# Power.net
KiCad netlist of a schematic drawn in Altium Designer
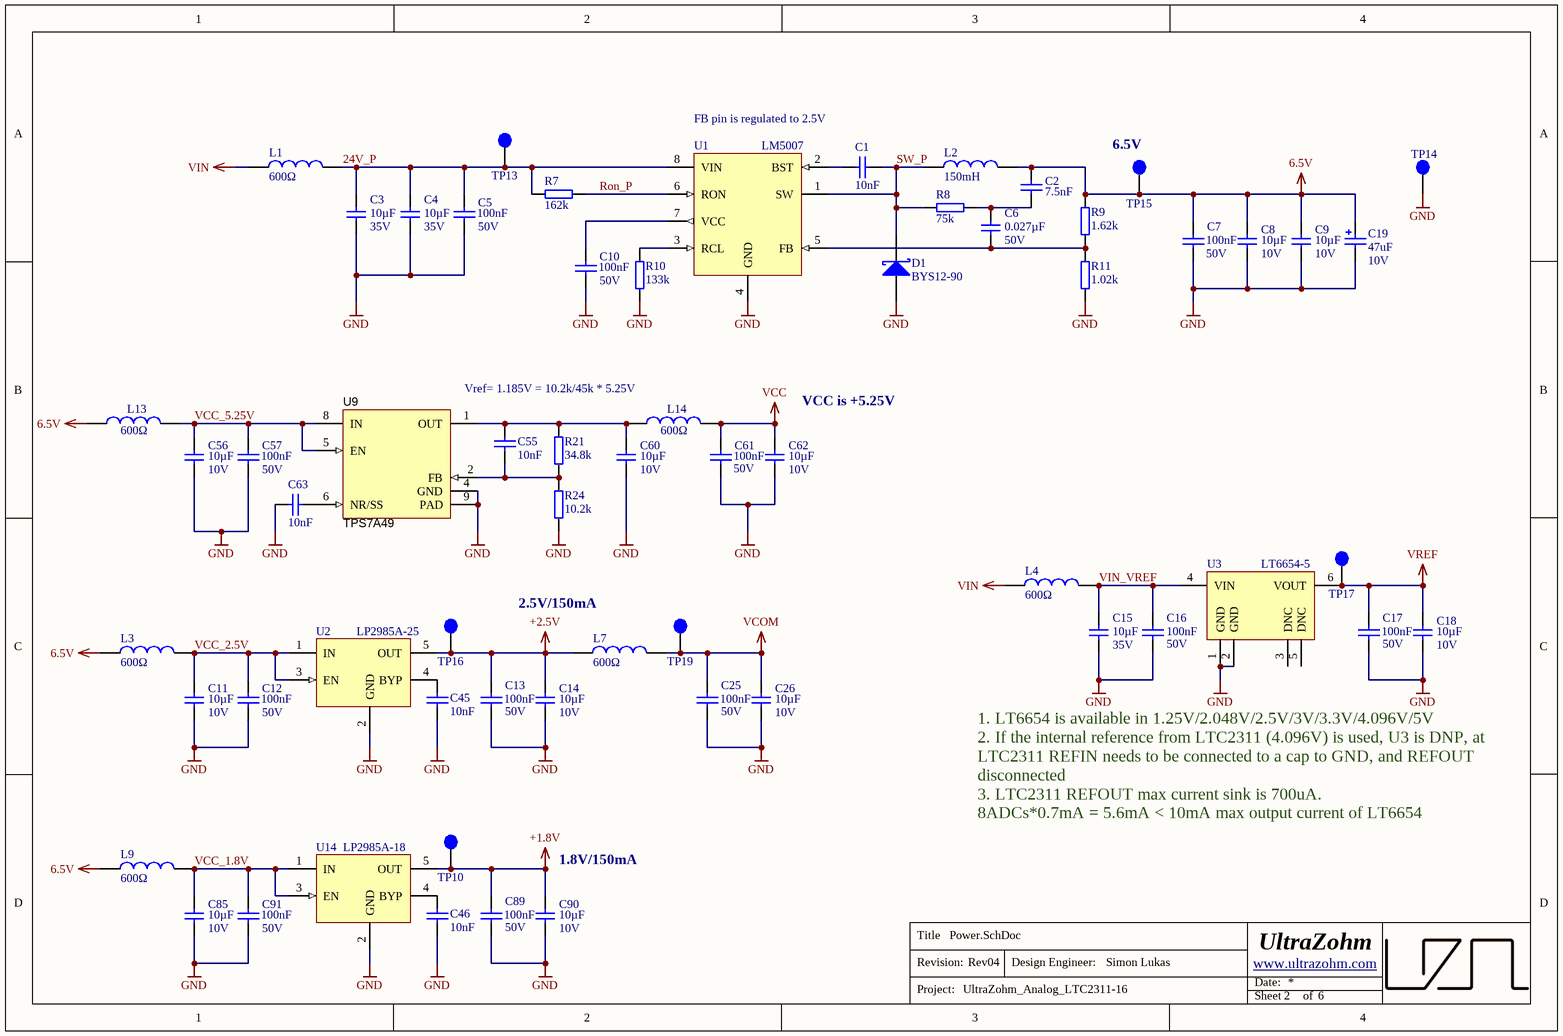
[diagram p0: Power.SchDoc]

(export (version "E")
  (design (tool "Eeschema 10.0.6"))
  (components
    (comp (ref "C1")
      (value "10nF")
      (footprint "CAPC1608X07N")
      (fields (field (name "MF") "Würth") (field (name "MPN") "885012206065") (field (name "VOLTAGE") "25V"))
      (libsource (lib "UltraZohm_ADC") (part "Cap_0603"))
    )
    (comp (ref "C2")
      (value "7.5nF")
      (footprint "CAPC1608X07N")
      (fields
        (field (name "MF") "KEMET")
        (field (name "MPN") "C0603C752J3GACTU")
        (field (name "VOLTAGE") "25V")
      )
      (libsource (lib "UltraZohm_ADC") (part "Cap_0603"))
    )
    (comp (ref "C3")
      (value "10µF")
      (footprint "C_1206")
      (description "Capacitor 1206")
      (fields (field (name "TOLERANCE") "20%") (field (name "MF") "AVX") (field (name "VOLTAGE") "35V"))
      (libsource (lib "UltraZohm_ADC") (part "C_1206"))
    )
    (comp (ref "C4")
      (value "10µF")
      (footprint "C_1206")
      (description "Capacitor 1206")
      (fields (field (name "TOLERANCE") "20%") (field (name "MF") "AVX") (field (name "VOLTAGE") "35V"))
      (libsource (lib "UltraZohm_ADC") (part "C_1206"))
    )
    (comp (ref "C5")
      (value "100nF")
      (footprint "CAPC1608X07N")
      (fields
        (field (name "MF") "Yageo")
        (field (name "MPN") "CC0603KRX7R9BB104")
        (field (name "VOLTAGE") "50V")
        (field (name "TOLERANCE") "10%")
      )
      (libsource (lib "UltraZohm_ADC") (part "Cap_0603"))
    )
    (comp (ref "C6")
      (value "0.027µF")
      (footprint "C_1206")
      (description "Capacitor 1206")
      (fields
        (field (name "TOLERANCE") "5%")
        (field (name "MF") "Murata")
        (field (name "VOLTAGE") "50V")
        (field (name "CREATED") "2018_06_25_AGeiger")
      )
      (libsource (lib "UltraZohm_ADC") (part "C_1206"))
    )
    (comp (ref "C7")
      (value "100nF")
      (footprint "CAPC1608X07N")
      (fields
        (field (name "MF") "Yageo")
        (field (name "MPN") "CC0603KRX7R9BB104")
        (field (name "VOLTAGE") "50V")
      )
      (libsource (lib "UltraZohm_ADC") (part "Cap_0603"))
    )
    (comp (ref "C8")
      (value "10µF")
      (footprint "C_1206")
      (description "Capacitor 1206")
      (fields
        (field (name "TOLERANCE") "10%")
        (field (name "MF") "Samsung Electro-Mechanics")
        (field (name "VOLTAGE") "10V")
        (field (name "CREATED") "2020_09_17_Liegmann")
      )
      (libsource (lib "UltraZohm_ADC") (part "C_1206"))
    )
    (comp (ref "C9")
      (value "10µF")
      (footprint "C_1206")
      (description "Capacitor 1206")
      (fields
        (field (name "TOLERANCE") "10%")
        (field (name "MF") "Samsung Electro-Mechanics")
        (field (name "VOLTAGE") "10V")
        (field (name "CREATED") "2020_09_17_Liegmann")
      )
      (libsource (lib "UltraZohm_ADC") (part "C_1206"))
    )
    (comp (ref "C10")
      (value "100nF")
      (footprint "CAPC1608X07N")
      (fields
        (field (name "MF") "Yageo")
        (field (name "MPN") "CC0603KRX7R9BB104")
        (field (name "VOLTAGE") "50V")
        (field (name "TOLERANCE") "10%")
      )
      (libsource (lib "UltraZohm_ADC") (part "Cap_0603"))
    )
    (comp (ref "C11")
      (value "10µF")
      (footprint "C_1206")
      (description "Capacitor 1206")
      (fields
        (field (name "TOLERANCE") "10%")
        (field (name "MF") "Samsung Electro-Mechanics")
        (field (name "VOLTAGE") "10V")
        (field (name "CREATED") "2020_09_17_Liegmann")
      )
      (libsource (lib "UltraZohm_ADC") (part "C_1206"))
    )
    (comp (ref "C12")
      (value "100nF")
      (footprint "CAPC1608X07N")
      (fields
        (field (name "MF") "Yageo")
        (field (name "MPN") "CC0603KRX7R9BB104")
        (field (name "VOLTAGE") "50V")
        (field (name "TOLERANCE") "10%")
      )
      (libsource (lib "UltraZohm_ADC") (part "Cap_0603"))
    )
    (comp (ref "C13")
      (value "100nF")
      (footprint "CAPC1608X07N")
      (fields
        (field (name "MF") "Yageo")
        (field (name "MPN") "CC0603KRX7R9BB104")
        (field (name "VOLTAGE") "50V")
      )
      (libsource (lib "UltraZohm_ADC") (part "Cap_0603"))
    )
    (comp (ref "C14")
      (value "10µF")
      (footprint "C_1206")
      (description "Capacitor 1206")
      (fields
        (field (name "TOLERANCE") "10%")
        (field (name "MF") "Samsung Electro-Mechanics")
        (field (name "VOLTAGE") "10V")
        (field (name "CREATED") "2020_09_17_Liegmann")
      )
      (libsource (lib "UltraZohm_ADC") (part "C_1206"))
    )
    (comp (ref "C15")
      (value "10µF")
      (footprint "C_1206")
      (description "Capacitor 1206")
      (fields (field (name "TOLERANCE") "20%") (field (name "MF") "AVX") (field (name "VOLTAGE") "35V"))
      (libsource (lib "UltraZohm_ADC") (part "C_1206"))
    )
    (comp (ref "C16")
      (value "100nF")
      (footprint "CAPC1608X07N")
      (fields
        (field (name "MF") "Yageo")
        (field (name "MPN") "CC0603KRX7R9BB104")
        (field (name "VOLTAGE") "50V")
      )
      (libsource (lib "UltraZohm_ADC") (part "Cap_0603"))
    )
    (comp (ref "C17")
      (value "100nF")
      (footprint "CAPC1608X07N")
      (fields
        (field (name "MF") "Yageo")
        (field (name "MPN") "CC0603KRX7R9BB104")
        (field (name "VOLTAGE") "50V")
      )
      (libsource (lib "UltraZohm_ADC") (part "Cap_0603"))
    )
    (comp (ref "C18")
      (value "10µF")
      (footprint "C_1206")
      (description "Capacitor 1206")
      (fields
        (field (name "TOLERANCE") "10%")
        (field (name "MF") "Samsung Electro-Mechanics")
        (field (name "VOLTAGE") "10V")
        (field (name "CREATED") "2020_09_17_Liegmann")
      )
      (libsource (lib "UltraZohm_ADC") (part "C_1206"))
    )
    (comp (ref "C19")
      (value "47uF")
      (footprint "WCAP-ASLI_5x5.5")
      (description "WCAP-ASLI Aluminum Electrolytic Capacitor, V-Chip, SMT, D5xH5.5mm, 47uF, 10V")
      (fields
        (field (name "MPN") "865080242004")
        (field (name "MF") "Wurth Elektronik")
        (field (name "VOLTAGE") "10V")
      )
      (libsource (lib "UltraZohm_ADC") (part "865080142007"))
    )
    (comp (ref "C25")
      (value "100nF")
      (footprint "CAPC1608X07N")
      (fields
        (field (name "MF") "Yageo")
        (field (name "MPN") "CC0603KRX7R9BB104")
        (field (name "VOLTAGE") "50V")
      )
      (libsource (lib "UltraZohm_ADC") (part "Cap_0603"))
    )
    (comp (ref "C26")
      (value "10µF")
      (footprint "C_1206")
      (description "Capacitor 1206")
      (fields
        (field (name "TOLERANCE") "10%")
        (field (name "MF") "Samsung Electro-Mechanics")
        (field (name "VOLTAGE") "10V")
        (field (name "CREATED") "2020_09_17_Liegmann")
      )
      (libsource (lib "UltraZohm_ADC") (part "C_1206"))
    )
    (comp (ref "C45")
      (value "10nF")
      (footprint "CAPC1608X07N")
      (fields (field (name "MF") "Würth") (field (name "MPN") "885012206065") (field (name "VOLTAGE") "25V"))
      (libsource (lib "UltraZohm_ADC") (part "Cap_0603"))
    )
    (comp (ref "C46")
      (value "10nF")
      (footprint "CAPC1608X07N")
      (fields (field (name "MF") "Würth") (field (name "MPN") "885012206065") (field (name "VOLTAGE") "25V"))
      (libsource (lib "UltraZohm_ADC") (part "Cap_0603"))
    )
    (comp (ref "C55")
      (value "10nF")
      (footprint "CAPC1608X07N")
      (fields
        (field (name "MF") "Würth Elektronik")
        (field (name "MPN") "885012206065")
        (field (name "VOLTAGE") "25V")
      )
      (libsource (lib "UltraZohm_ADC") (part "Cap_0603"))
    )
    (comp (ref "C56")
      (value "10µF")
      (footprint "C_1206")
      (description "Capacitor 1206")
      (fields
        (field (name "TOLERANCE") "10%")
        (field (name "MF") "Samsung Electro-Mechanics")
        (field (name "VOLTAGE") "10V")
        (field (name "CREATED") "2020_09_17_Liegmann")
      )
      (libsource (lib "UltraZohm_ADC") (part "C_1206"))
    )
    (comp (ref "C57")
      (value "100nF")
      (footprint "CAPC1608X07N")
      (fields
        (field (name "MF") "Yageo")
        (field (name "MPN") "CC0603KRX7R9BB104")
        (field (name "VOLTAGE") "50V")
        (field (name "TOLERANCE") "10%")
      )
      (libsource (lib "UltraZohm_ADC") (part "Cap_0603"))
    )
    (comp (ref "C60")
      (value "10µF")
      (footprint "C_1206")
      (description "Capacitor 1206")
      (fields
        (field (name "TOLERANCE") "10%")
        (field (name "MF") "Samsung Electro-Mechanics")
        (field (name "VOLTAGE") "10V")
        (field (name "CREATED") "2020_09_17_Liegmann")
      )
      (libsource (lib "UltraZohm_ADC") (part "C_1206"))
    )
    (comp (ref "C61")
      (value "100nF")
      (footprint "CAPC1608X07N")
      (fields
        (field (name "MF") "Yageo")
        (field (name "MPN") "CC0603KRX7R9BB104")
        (field (name "VOLTAGE") "50V")
        (field (name "TOLERANCE") "10%")
      )
      (libsource (lib "UltraZohm_ADC") (part "Cap_0603"))
    )
    (comp (ref "C62")
      (value "10µF")
      (footprint "C_1206")
      (description "Capacitor 1206")
      (fields
        (field (name "TOLERANCE") "10%")
        (field (name "MF") "Samsung Electro-Mechanics")
        (field (name "VOLTAGE") "10V")
        (field (name "CREATED") "2020_09_17_Liegmann")
      )
      (libsource (lib "UltraZohm_ADC") (part "C_1206"))
    )
    (comp (ref "C63")
      (value "10nF")
      (footprint "CAPC1608X07N")
      (fields
        (field (name "MF") "Würth Elektronik")
        (field (name "MPN") "885012206065")
        (field (name "VOLTAGE") "25V")
      )
      (libsource (lib "UltraZohm_ADC") (part "Cap_0603"))
    )
    (comp (ref "C85")
      (value "10µF")
      (footprint "C_1206")
      (description "Capacitor 1206")
      (fields
        (field (name "TOLERANCE") "10%")
        (field (name "MF") "Samsung Electro-Mechanics")
        (field (name "VOLTAGE") "10V")
        (field (name "CREATED") "2020_09_17_Liegmann")
      )
      (libsource (lib "UltraZohm_ADC") (part "C_1206"))
    )
    (comp (ref "C89")
      (value "100nF")
      (footprint "CAPC1608X07N")
      (fields
        (field (name "MF") "Yageo")
        (field (name "MPN") "CC0603KRX7R9BB104")
        (field (name "VOLTAGE") "50V")
      )
      (libsource (lib "UltraZohm_ADC") (part "Cap_0603"))
    )
    (comp (ref "C90")
      (value "10µF")
      (footprint "C_1206")
      (description "Capacitor 1206")
      (fields
        (field (name "TOLERANCE") "10%")
        (field (name "MF") "Samsung Electro-Mechanics")
        (field (name "VOLTAGE") "10V")
        (field (name "CREATED") "2020_09_17_Liegmann")
      )
      (libsource (lib "UltraZohm_ADC") (part "C_1206"))
    )
    (comp (ref "C91")
      (value "100nF")
      (footprint "CAPC1608X07N")
      (fields
        (field (name "MF") "Yageo")
        (field (name "MPN") "CC0603KRX7R9BB104")
        (field (name "VOLTAGE") "50V")
        (field (name "TOLERANCE") "10%")
      )
      (libsource (lib "UltraZohm_ADC") (part "Cap_0603"))
    )
    (comp (ref "D1")
      (value "BYS12-90")
      (footprint "DIOM4227X23N")
      (description "Schottky Diode")
      (fields (field (name "MF") "Vishay") (field (name "MPN") "BYS12-90-E3/TR3"))
      (libsource (lib "UltraZohm_ADC") (part "BYS12-90"))
    )
    (comp (ref "L1")
      (value "600Ω")
      (footprint "WE-CBF_0805_High Current")
      (description "WE-CBF SMD EMI Suppression Ferrite Bead, 0805, 600Ω")
      (fields (field (name "MF") "Wurth Elektronik") (field (name "MPN") "742792040"))
      (libsource (lib "UltraZohm_ADC") (part "WE-CBF, 742792040"))
    )
    (comp (ref "L2")
      (value "150mH")
      (footprint "SMT_inductor_1050_Performance")
      (description "SMT power Inductor, 150uH, 320m DRC")
      (fields (field (name "MF") "EPCOS / TDK") (field (name "MPN") "B82464G4154M"))
      (libsource (lib "UltraZohm_ADC") (part "B82464G4154M"))
    )
    (comp (ref "L3")
      (value "600Ω")
      (footprint "WE-CBF_0805_High Current")
      (description "WE-CBF SMD EMI Suppression Ferrite Bead, 0805, 600Ω")
      (fields (field (name "MF") "Wurth Elektronik") (field (name "MPN") "742792040"))
      (libsource (lib "UltraZohm_ADC") (part "WE-CBF, 742792040"))
    )
    (comp (ref "L4")
      (value "600Ω")
      (footprint "WE-CBF_0805_High Current")
      (description "WE-CBF SMD EMI Suppression Ferrite Bead, 0805, 600Ω")
      (fields (field (name "MF") "Wurth Elektronik") (field (name "MPN") "742792040"))
      (libsource (lib "UltraZohm_ADC") (part "WE-CBF, 742792040"))
    )
    (comp (ref "L7")
      (value "600Ω")
      (footprint "WE-CBF_0805_High Current")
      (description "WE-CBF SMD EMI Suppression Ferrite Bead, 0805, 600Ω")
      (fields (field (name "MF") "Wurth Elektronik") (field (name "MPN") "742792040"))
      (libsource (lib "UltraZohm_ADC") (part "WE-CBF, 742792040"))
    )
    (comp (ref "L9")
      (value "600Ω")
      (footprint "WE-CBF_0805_High Current")
      (description "WE-CBF SMD EMI Suppression Ferrite Bead, 0805, 600Ω")
      (fields (field (name "MF") "Wurth Elektronik") (field (name "MPN") "742792040"))
      (libsource (lib "UltraZohm_ADC") (part "WE-CBF, 742792040"))
    )
    (comp (ref "L13")
      (value "600Ω")
      (footprint "WE-CBF_0805_High Current")
      (description "WE-CBF SMD EMI Suppression Ferrite Bead, 0805, 600Ω")
      (fields (field (name "MF") "Würth Elektronik") (field (name "MPN") "742792040"))
      (libsource (lib "UltraZohm_ADC") (part "WE-CBF, 742792040"))
    )
    (comp (ref "L14")
      (value "600Ω")
      (footprint "WE-CBF_0805_High Current")
      (description "WE-CBF SMD EMI Suppression Ferrite Bead, 0805, 600Ω")
      (fields (field (name "MF") "Würth Elektronik") (field (name "MPN") "742792040"))
      (libsource (lib "UltraZohm_ADC") (part "WE-CBF, 742792040"))
    )
    (comp (ref "R7")
      (value "162k")
      (footprint "RESC1608X06N")
      (fields (field (name "MF") "Bourns") (field (name "MPN") "CR0603-FX-1623ELF"))
      (libsource (lib "UltraZohm_ADC") (part "R_0603"))
    )
    (comp (ref "R8")
      (value "75k")
      (footprint "RESC1608X06N")
      (fields (field (name "MF") "Yageo") (field (name "MPN") "AC0603FR-1375KL"))
      (libsource (lib "UltraZohm_ADC") (part "R_0603"))
    )
    (comp (ref "R9")
      (value "1.62k")
      (footprint "RESC1608X06N")
      (fields
        (field (name "MF") "Bourns")
        (field (name "MPN") "CR0603-FX-1621ELF")
        (field (name "TOLERANCE") "1%")
      )
      (libsource (lib "UltraZohm_ADC") (part "R_0603"))
    )
    (comp (ref "R10")
      (value "133k")
      (footprint "RESC1608X06N")
      (fields (field (name "MF") "Bourns") (field (name "MPN") "CR0603-FX-1333ELF"))
      (libsource (lib "UltraZohm_ADC") (part "R_0603"))
    )
    (comp (ref "R11")
      (value "1.02k")
      (footprint "RESC1608X06N")
      (fields
        (field (name "MF") "Bourns")
        (field (name "MPN") "CR0603-FX-1021ELF")
        (field (name "TOLERANCE") "1%")
      )
      (libsource (lib "UltraZohm_ADC") (part "R_0603"))
    )
    (comp (ref "R21")
      (value "34.8k")
      (footprint "RESC1608X06N")
      (fields
        (field (name "MF") "Bourns")
        (field (name "MPN") "CR0603-FX-3482ELF")
        (field (name "TOLERANCE") "1%")
      )
      (libsource (lib "UltraZohm_ADC") (part "R_0603"))
    )
    (comp (ref "R24")
      (value "10.2k")
      (footprint "RESC1608X06N")
      (fields
        (field (name "MF") "Bourns")
        (field (name "MPN") "CR0603-FX-1022ELF")
        (field (name "TOLERANCE") "1%")
      )
      (libsource (lib "UltraZohm_ADC") (part "R_0603"))
    )
    (comp (ref "TP10")
      (value "+1.8V")
      (footprint "TP_1mm")
      (description "Testpoint 1mm")
      (fields (field (name "CREATED") "2018_06_25_AGeiger"))
      (libsource (lib "UltraZOhm_CarrierBoard") (part "TP_1mm"))
    )
    (comp (ref "TP13")
      (value "VIN")
      (footprint "TP_1mm")
      (description "Testpoint 1mm")
      (fields (field (name "CREATED") "2018_06_25_AGeiger"))
      (libsource (lib "UltraZOhm_CarrierBoard") (part "TP_1mm"))
    )
    (comp (ref "TP14")
      (value "GND")
      (footprint "TP_1mm")
      (description "Testpoint 1mm")
      (fields (field (name "CREATED") "2018_06_25_AGeiger"))
      (libsource (lib "UltraZOhm_CarrierBoard") (part "TP_1mm"))
    )
    (comp (ref "TP15")
      (value "+5V")
      (footprint "TP_1mm")
      (description "Testpoint 1mm")
      (fields (field (name "CREATED") "2018_06_25_AGeiger"))
      (libsource (lib "UltraZOhm_CarrierBoard") (part "TP_1mm"))
    )
    (comp (ref "TP16")
      (value "OVCC")
      (footprint "TP_1mm")
      (description "Testpoint 1mm")
      (fields (field (name "CREATED") "2018_06_25_AGeiger"))
      (libsource (lib "UltraZOhm_CarrierBoard") (part "TP_1mm"))
    )
    (comp (ref "TP17")
      (value "VREF")
      (footprint "TP_1mm")
      (description "Testpoint 1mm")
      (fields (field (name "CREATED") "2018_06_25_AGeiger"))
      (libsource (lib "UltraZOhm_CarrierBoard") (part "TP_1mm"))
    )
    (comp (ref "TP19")
      (value "VCOM")
      (footprint "TP_1mm")
      (description "Testpoint 1mm")
      (fields (field (name "CREATED") "2018_06_25_AGeiger"))
      (libsource (lib "UltraZOhm_CarrierBoard") (part "TP_1mm"))
    )
    (comp (ref "U1")
      (value "LM5007")
      (footprint "TSOP65P490X110-8N")
      (description "Buck Converter, 9-75Vin, 2.5-73Vout")
      (fields (field (name "MF") "Texas Instruments") (field (name "MPN") "LM5007MM/NOPB"))
      (libsource (lib "UltraZohm_ADC") (part "LM5007"))
    )
    (comp (ref "U2")
      (value "LP2985A-25")
      (footprint "SOT95P250X110-5N")
      (description "150mA, LDO, Vout = 2.5V, Vin,max = 16V")
      (fields (field (name "MF") "Texas Instruments"))
      (libsource (lib "UltraZohm_ADC") (part "LP2985A-25"))
    )
    (comp (ref "U3")
      (value "LT6654-5")
      (footprint "SOT95P280X100-6N")
      (fields (field (name "MF") "Analog Devices") (field (name "MPN") "LT6654AIS6-5#TRMPBF"))
      (libsource (lib "UltraZohm_ADC") (part "LT6654"))
    )
    (comp (ref "U9")
      (value "TPS7A49")
      (footprint "DGN0008D_N")
      (description "+36V, +150mA, Ultralow-Noise, Positive LINEAR REGULATOR, DGN0008D")
      (fields (field (name "MPN") "TPS7A4901DGN") (field (name "MF") "Texas Instruments"))
      (libsource (lib "UltraZohm_ADC") (part "TPS7A4901DGN"))
    )
    (comp (ref "U14")
      (value "LP2985A-18")
      (footprint "SOT95P250X110-5N")
      (description "150mA, LDO, Vout = 1.8V , Vin,max = 16V")
      (libsource (lib "UltraZohm_ADC") (part "LP2985A-18"))
    )
  )
  (nets
    (net (code "1") (name "+1.8V") (class "Default")
      (node (ref "C89") (pin "1") (pinfunction "1_1") (pintype "passive"))
      (node (ref "C90") (pin "2") (pinfunction "2_2") (pintype "passive"))
      (node (ref "TP10") (pin "1") (pintype "passive"))
      (node (ref "U14") (pin "5") (pinfunction "OUT_5") (pintype "power_in"))
    )
    (net (code "2") (name "+2.5V") (class "Default")
      (node (ref "C13") (pin "1") (pinfunction "1_1") (pintype "passive"))
      (node (ref "C14") (pin "2") (pinfunction "2_2") (pintype "passive"))
      (node (ref "L7") (pin "1") (pinfunction "1_1") (pintype "passive"))
      (node (ref "TP16") (pin "1") (pintype "passive"))
      (node (ref "U2") (pin "5") (pinfunction "OUT_5") (pintype "power_in"))
    )
    (net (code "3") (name "/24V_P") (class "Default")
      (node (ref "C3") (pin "2") (pinfunction "2_2") (pintype "passive"))
      (node (ref "C4") (pin "2") (pinfunction "2_2") (pintype "passive"))
      (node (ref "C5") (pin "1") (pinfunction "1_1") (pintype "passive"))
      (node (ref "L1") (pin "2") (pinfunction "2_2") (pintype "passive"))
      (node (ref "R7") (pin "1") (pintype "passive"))
      (node (ref "TP13") (pin "1") (pintype "passive"))
      (node (ref "U1") (pin "8") (pinfunction "VIN_8") (pintype "power_in"))
    )
    (net (code "4") (name "/Ron_P") (class "Default")
      (node (ref "R7") (pin "2") (pintype "passive"))
      (node (ref "U1") (pin "6") (pinfunction "RON_6") (pintype "input"))
    )
    (net (code "5") (name "/SW_P") (class "Default")
      (node (ref "C1") (pin "2") (pinfunction "2_2") (pintype "passive"))
      (node (ref "D1") (pin "1") (pinfunction "K_1") (pintype "passive"))
      (node (ref "L2") (pin "1") (pinfunction "1_1") (pintype "passive"))
      (node (ref "R8") (pin "1") (pintype "passive"))
      (node (ref "U1") (pin "1") (pinfunction "SW_1") (pintype "power_in"))
    )
    (net (code "6") (name "/VCC_1.8V") (class "Default")
      (node (ref "C85") (pin "2") (pinfunction "2_2") (pintype "passive"))
      (node (ref "C91") (pin "1") (pinfunction "1_1") (pintype "passive"))
      (node (ref "L9") (pin "2") (pinfunction "2_2") (pintype "passive"))
      (node (ref "U14") (pin "1") (pinfunction "IN_1") (pintype "power_in"))
      (node (ref "U14") (pin "3") (pinfunction "EN_3") (pintype "input"))
    )
    (net (code "7") (name "/VCC_2.5V") (class "Default")
      (node (ref "C11") (pin "2") (pinfunction "2_2") (pintype "passive"))
      (node (ref "C12") (pin "1") (pinfunction "1_1") (pintype "passive"))
      (node (ref "L3") (pin "2") (pinfunction "2_2") (pintype "passive"))
      (node (ref "U2") (pin "1") (pinfunction "IN_1") (pintype "power_in"))
      (node (ref "U2") (pin "3") (pinfunction "EN_3") (pintype "input"))
    )
    (net (code "8") (name "/VCC_5.25V") (class "Default")
      (node (ref "C56") (pin "2") (pinfunction "2_2") (pintype "passive"))
      (node (ref "C57") (pin "1") (pinfunction "1_1") (pintype "passive"))
      (node (ref "L13") (pin "2") (pinfunction "2_2") (pintype "passive"))
      (node (ref "U9") (pin "5") (pinfunction "EN_5") (pintype "input"))
      (node (ref "U9") (pin "8") (pinfunction "IN_8") (pintype "power_in"))
    )
    (net (code "9") (name "/VIN_VREF") (class "Default")
      (node (ref "C15") (pin "2") (pinfunction "2_2") (pintype "passive"))
      (node (ref "C16") (pin "1") (pinfunction "1_1") (pintype "passive"))
      (node (ref "L4") (pin "2") (pinfunction "2_2") (pintype "passive"))
      (node (ref "U3") (pin "4") (pinfunction "VIN_4") (pintype "power_in"))
    )
    (net (code "10") (name "6.5V") (class "Default")
      (node (ref "C19") (pin "2") (pinfunction "P_2") (pintype "passive"))
      (node (ref "C2") (pin "1") (pinfunction "1_1") (pintype "passive"))
      (node (ref "C7") (pin "2") (pinfunction "2_2") (pintype "passive"))
      (node (ref "C8") (pin "2") (pinfunction "2_2") (pintype "passive"))
      (node (ref "C9") (pin "2") (pinfunction "2_2") (pintype "passive"))
      (node (ref "L13") (pin "1") (pinfunction "1_1") (pintype "passive"))
      (node (ref "L2") (pin "2") (pinfunction "2_2") (pintype "passive"))
      (node (ref "L3") (pin "1") (pinfunction "1_1") (pintype "passive"))
      (node (ref "L9") (pin "1") (pinfunction "1_1") (pintype "passive"))
      (node (ref "R9") (pin "2") (pintype "passive"))
      (node (ref "TP15") (pin "1") (pintype "passive"))
    )
    (net (code "11") (name "GND") (class "Default")
      (node (ref "C10") (pin "2") (pinfunction "2_2") (pintype "passive"))
      (node (ref "C11") (pin "1") (pinfunction "1_1") (pintype "passive"))
      (node (ref "C12") (pin "2") (pinfunction "2_2") (pintype "passive"))
      (node (ref "C13") (pin "2") (pinfunction "2_2") (pintype "passive"))
      (node (ref "C14") (pin "1") (pinfunction "1_1") (pintype "passive"))
      (node (ref "C15") (pin "1") (pinfunction "1_1") (pintype "passive"))
      (node (ref "C16") (pin "2") (pinfunction "2_2") (pintype "passive"))
      (node (ref "C17") (pin "2") (pinfunction "2_2") (pintype "passive"))
      (node (ref "C18") (pin "1") (pinfunction "1_1") (pintype "passive"))
      (node (ref "C19") (pin "1") (pinfunction "N_1") (pintype "passive"))
      (node (ref "C25") (pin "2") (pinfunction "2_2") (pintype "passive"))
      (node (ref "C26") (pin "1") (pinfunction "1_1") (pintype "passive"))
      (node (ref "C3") (pin "1") (pinfunction "1_1") (pintype "passive"))
      (node (ref "C4") (pin "1") (pinfunction "1_1") (pintype "passive"))
      (node (ref "C45") (pin "1") (pinfunction "1_1") (pintype "passive"))
      (node (ref "C46") (pin "1") (pinfunction "1_1") (pintype "passive"))
      (node (ref "C5") (pin "2") (pinfunction "2_2") (pintype "passive"))
      (node (ref "C56") (pin "1") (pinfunction "1_1") (pintype "passive"))
      (node (ref "C57") (pin "2") (pinfunction "2_2") (pintype "passive"))
      (node (ref "C60") (pin "1") (pinfunction "1_1") (pintype "passive"))
      (node (ref "C61") (pin "1") (pinfunction "1_1") (pintype "passive"))
      (node (ref "C62") (pin "1") (pinfunction "1_1") (pintype "passive"))
      (node (ref "C63") (pin "2") (pinfunction "2_2") (pintype "passive"))
      (node (ref "C7") (pin "1") (pinfunction "1_1") (pintype "passive"))
      (node (ref "C8") (pin "1") (pinfunction "1_1") (pintype "passive"))
      (node (ref "C85") (pin "1") (pinfunction "1_1") (pintype "passive"))
      (node (ref "C89") (pin "2") (pinfunction "2_2") (pintype "passive"))
      (node (ref "C9") (pin "1") (pinfunction "1_1") (pintype "passive"))
      (node (ref "C90") (pin "1") (pinfunction "1_1") (pintype "passive"))
      (node (ref "C91") (pin "2") (pinfunction "2_2") (pintype "passive"))
      (node (ref "D1") (pin "2") (pinfunction "A_2") (pintype "passive"))
      (node (ref "R10") (pin "1") (pintype "passive"))
      (node (ref "R11") (pin "1") (pintype "passive"))
      (node (ref "R24") (pin "2") (pintype "passive"))
      (node (ref "TP14") (pin "1") (pintype "passive"))
      (node (ref "U1") (pin "4") (pinfunction "GND_4") (pintype "power_in"))
      (node (ref "U14") (pin "2") (pinfunction "GND_2") (pintype "power_in"))
      (node (ref "U2") (pin "2") (pinfunction "GND_2") (pintype "power_in"))
      (node (ref "U3") (pin "1") (pinfunction "GND_1") (pintype "power_in"))
      (node (ref "U3") (pin "2") (pinfunction "GND_2") (pintype "power_in"))
      (node (ref "U9") (pin "4") (pinfunction "GND_4") (pintype "power_in"))
      (node (ref "U9") (pin "9") (pinfunction "PAD_9") (pintype "power_in"))
    )
    (net (code "12") (name "Net-(C2-Pad2)") (class "Default")
      (node (ref "C2") (pin "2") (pinfunction "2_2") (pintype "passive"))
      (node (ref "C6") (pin "2") (pinfunction "2_2") (pintype "passive"))
      (node (ref "R8") (pin "2") (pintype "passive"))
    )
    (net (code "13") (name "Net-(U1-BST)") (class "Default")
      (node (ref "C1") (pin "1") (pinfunction "1_1") (pintype "passive"))
      (node (ref "U1") (pin "2") (pinfunction "BST_2") (pintype "input"))
    )
    (net (code "14") (name "Net-(U1-FB)") (class "Default")
      (node (ref "C6") (pin "1") (pinfunction "1_1") (pintype "passive"))
      (node (ref "R11") (pin "2") (pintype "passive"))
      (node (ref "R9") (pin "1") (pintype "passive"))
      (node (ref "U1") (pin "5") (pinfunction "FB_5") (pintype "input"))
    )
    (net (code "15") (name "Net-(U1-RCL)") (class "Default")
      (node (ref "R10") (pin "2") (pintype "passive"))
      (node (ref "U1") (pin "3") (pinfunction "RCL_3") (pintype "input"))
    )
    (net (code "16") (name "Net-(U1-VCC)") (class "Default")
      (node (ref "C10") (pin "1") (pinfunction "1_1") (pintype "passive"))
      (node (ref "U1") (pin "7") (pinfunction "VCC_7") (pintype "output"))
    )
    (net (code "17") (name "Net-(U2-BYP)") (class "Default")
      (node (ref "C45") (pin "2") (pinfunction "2_2") (pintype "passive"))
      (node (ref "U2") (pin "4") (pinfunction "BYP_4") (pintype "passive"))
    )
    (net (code "18") (name "Net-(U9-FB)") (class "Default")
      (node (ref "C55") (pin "2") (pinfunction "2_2") (pintype "passive"))
      (node (ref "R21") (pin "2") (pintype "passive"))
      (node (ref "R24") (pin "1") (pintype "passive"))
      (node (ref "U9") (pin "2") (pinfunction "FB_2") (pintype "input"))
    )
    (net (code "19") (name "Net-(U9-NR{slash}SS)") (class "Default")
      (node (ref "C63") (pin "1") (pinfunction "1_1") (pintype "passive"))
      (node (ref "U9") (pin "6") (pinfunction "NR/SS_6") (pintype "input"))
    )
    (net (code "20") (name "Net-(U9-OUT)") (class "Default")
      (node (ref "C55") (pin "1") (pinfunction "1_1") (pintype "passive"))
      (node (ref "C60") (pin "2") (pinfunction "2_2") (pintype "passive"))
      (node (ref "L14") (pin "1") (pinfunction "1_1") (pintype "passive"))
      (node (ref "R21") (pin "1") (pintype "passive"))
      (node (ref "U9") (pin "1") (pinfunction "OUT_1") (pintype "power_in"))
    )
    (net (code "21") (name "Net-(U14-BYP)") (class "Default")
      (node (ref "C46") (pin "2") (pinfunction "2_2") (pintype "passive"))
      (node (ref "U14") (pin "4") (pinfunction "BYP_4") (pintype "passive"))
    )
    (net (code "22") (name "VCC") (class "Default")
      (node (ref "C61") (pin "2") (pinfunction "2_2") (pintype "passive"))
      (node (ref "C62") (pin "2") (pinfunction "2_2") (pintype "passive"))
      (node (ref "L14") (pin "2") (pinfunction "2_2") (pintype "passive"))
    )
    (net (code "23") (name "VCOM") (class "Default")
      (node (ref "C25") (pin "1") (pinfunction "1_1") (pintype "passive"))
      (node (ref "C26") (pin "2") (pinfunction "2_2") (pintype "passive"))
      (node (ref "L7") (pin "2") (pinfunction "2_2") (pintype "passive"))
      (node (ref "TP19") (pin "1") (pintype "passive"))
    )
    (net (code "24") (name "VIN") (class "Default")
      (node (ref "L1") (pin "1") (pinfunction "1_1") (pintype "passive"))
      (node (ref "L4") (pin "1") (pinfunction "1_1") (pintype "passive"))
    )
    (net (code "25") (name "VREF") (class "Default")
      (node (ref "C17") (pin "1") (pinfunction "1_1") (pintype "passive"))
      (node (ref "C18") (pin "2") (pinfunction "2_2") (pintype "passive"))
      (node (ref "TP17") (pin "1") (pintype "passive"))
      (node (ref "U3") (pin "6") (pinfunction "VOUT_6") (pintype "power_in"))
    )
    (net (code "26") (name "unconnected-(U3-DNC-Pad3)") (class "Default")
      (node (ref "U3") (pin "3") (pinfunction "DNC_3") (pintype "passive"))
    )
    (net (code "27") (name "unconnected-(U3-DNC-Pad5)") (class "Default")
      (node (ref "U3") (pin "5") (pinfunction "DNC_5") (pintype "passive"))
    )
    (net (code "28") (name "unconnected-(U9-DNC-Pad7)") (class "Default")
      (node (ref "U9") (pin "7") (pinfunction "DNC_7") (pintype "passive"))
    )
    (net (code "29") (name "unconnected-(U9-NC-Pad3)") (class "Default")
      (node (ref "U9") (pin "3") (pinfunction "NC_3") (pintype "passive"))
    )
  )
)
